# DIGI_PTT_CW.net
KiCad netlist of a schematic drawn in EAGLE
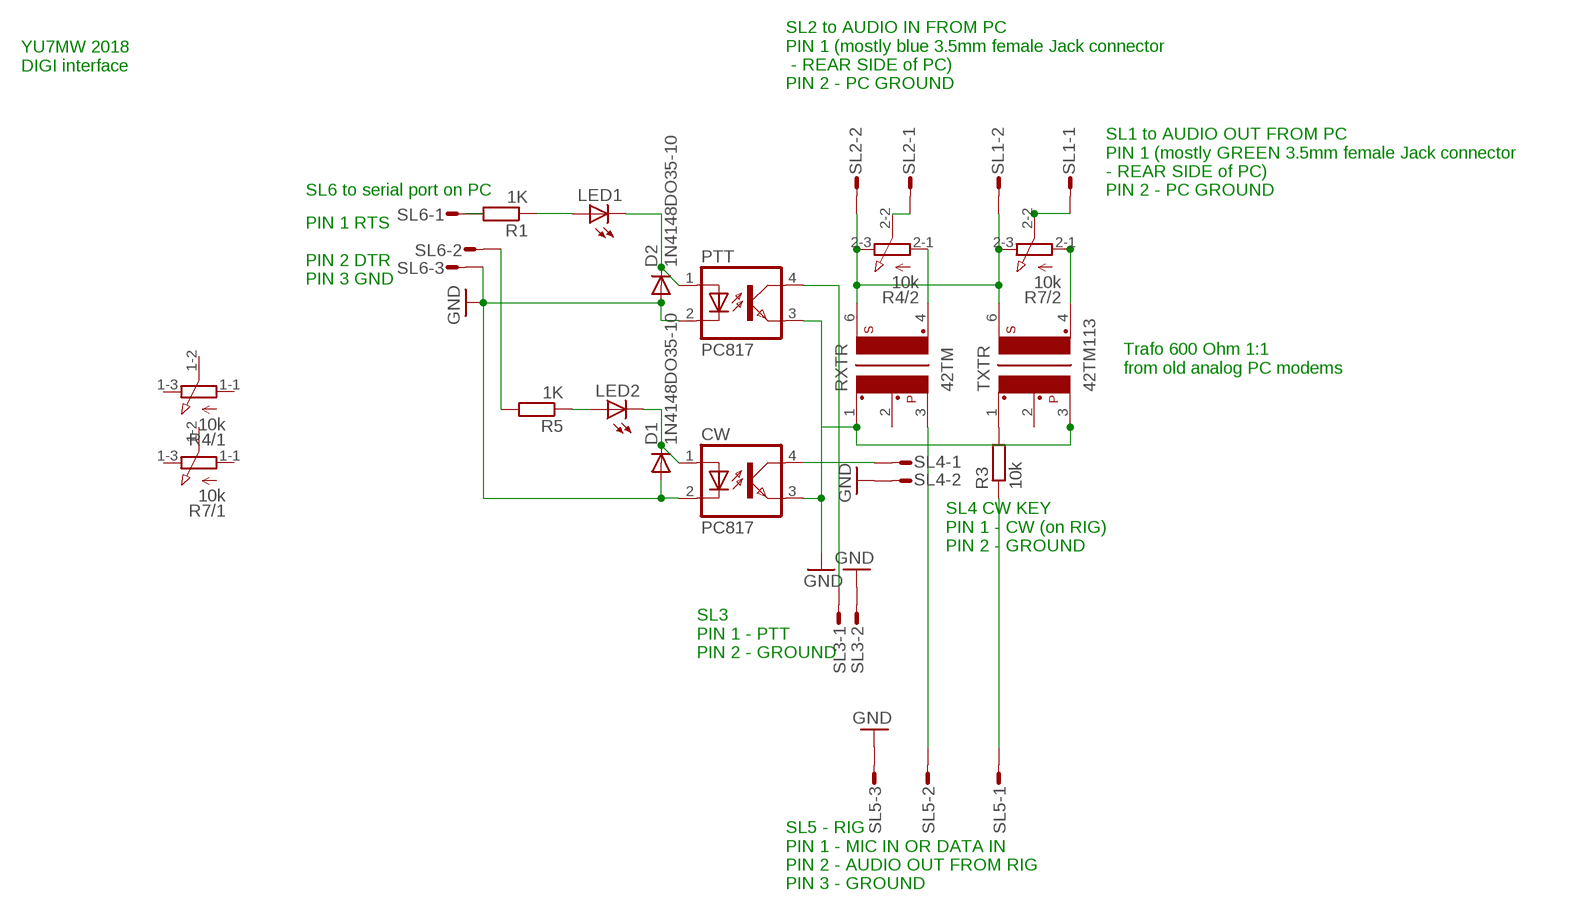
[diagram p0: schematic, sheet 1]

(export (version "E")
  (design (tool "Eeschema 10.0.6"))
  (components
    (comp (ref "CW")
      (value "PC817")
      (footprint "eagle-import:DIL04")
      (fields (field (name "MPN") "PC817X4J000F"))
      (libsource (lib "eagle-import") (part "PC817"))
    )
    (comp (ref "D1")
      (value "1N4148DO35-10")
      (footprint "eagle-import:DO35-10")
      (libsource (lib "eagle-import") (part "1N4148DO35-10"))
    )
    (comp (ref "D2")
      (value "1N4148DO35-10")
      (footprint "eagle-import:DO35-10")
      (libsource (lib "eagle-import") (part "1N4148DO35-10"))
    )
    (comp (ref "LED1")
      (value "LED3MM")
      (footprint "eagle-import:LED3MM")
      (libsource (lib "eagle-import") (part "LED3MM"))
    )
    (comp (ref "LED2")
      (value "LED3MM")
      (footprint "eagle-import:LED3MM")
      (libsource (lib "eagle-import") (part "LED3MM"))
    )
    (comp (ref "PTT")
      (value "PC817")
      (footprint "eagle-import:DIL04")
      (fields (field (name "MPN") "PC817X4J000F"))
      (libsource (lib "eagle-import") (part "PC817"))
    )
    (comp (ref "R1")
      (value "1K")
      (footprint "eagle-import:0207_10")
      (libsource (lib "eagle-import") (part "R-EU_0207/10"))
    )
    (comp (ref "R3")
      (value "10k")
      (footprint "eagle-import:0207_10")
      (libsource (lib "eagle-import") (part "R-EU_0207/10"))
    )
    (comp (ref "R4")
      (value "10k")
      (footprint "eagle-import:3RP_1610G")
      (libsource (lib "eagle-import") (part "3RP/1610G"))
    )
    (comp (ref "R5")
      (value "1K")
      (footprint "eagle-import:0207_10")
      (libsource (lib "eagle-import") (part "R-EU_0207/10"))
    )
    (comp (ref "R7")
      (value "10k")
      (footprint "eagle-import:3RP_1610G")
      (libsource (lib "eagle-import") (part "3RP/1610G"))
    )
    (comp (ref "RXTR")
      (value "42TM")
      (footprint "eagle-import:42TM")
      (libsource (lib "eagle-import") (part "42TM113"))
    )
    (comp (ref "SL1")
      (value "M02S")
      (footprint "eagle-import:02P")
      (libsource (lib "eagle-import") (part "M02S"))
    )
    (comp (ref "SL2")
      (value "M02S")
      (footprint "eagle-import:02P")
      (libsource (lib "eagle-import") (part "M02S"))
    )
    (comp (ref "SL3")
      (value "M02S")
      (footprint "eagle-import:02P")
      (libsource (lib "eagle-import") (part "M02S"))
    )
    (comp (ref "SL4")
      (value "M02S")
      (footprint "eagle-import:02P")
      (libsource (lib "eagle-import") (part "M02S"))
    )
    (comp (ref "SL5")
      (value "M03S")
      (footprint "eagle-import:03P")
      (libsource (lib "eagle-import") (part "M03S"))
    )
    (comp (ref "SL6")
      (value "M03S")
      (footprint "eagle-import:03P")
      (libsource (lib "eagle-import") (part "M03S"))
    )
    (comp (ref "TXTR")
      (value "42TM113")
      (footprint "eagle-import:42TM")
      (libsource (lib "eagle-import") (part "42TM113"))
    )
  )
  (nets
    (net (code "1") (name "GND") (class "Default")
      (node (ref "CW") (pin "2") (pinfunction "C_2") (pintype "passive"))
      (node (ref "CW") (pin "3") (pinfunction "EMIT_3") (pintype "passive"))
      (node (ref "D1") (pin "A") (pinfunction "A_A") (pintype "passive"))
      (node (ref "D2") (pin "A") (pinfunction "A_A") (pintype "passive"))
      (node (ref "PTT") (pin "2") (pinfunction "C_2") (pintype "passive"))
      (node (ref "PTT") (pin "3") (pinfunction "EMIT_3") (pintype "passive"))
      (node (ref "RXTR") (pin "1") (pinfunction "1_1") (pintype "passive"))
      (node (ref "SL3") (pin "2") (pinfunction "S_2") (pintype "passive"))
      (node (ref "SL4") (pin "2") (pinfunction "S_2") (pintype "passive"))
      (node (ref "SL5") (pin "3") (pinfunction "S_3") (pintype "passive"))
      (node (ref "SL6") (pin "3") (pinfunction "S_3") (pintype "passive"))
      (node (ref "TXTR") (pin "3") (pinfunction "3_3") (pintype "passive"))
    )
    (net (code "2") (name "Net-(CW-A)") (class "Default")
      (node (ref "CW") (pin "1") (pinfunction "A_1") (pintype "passive"))
      (node (ref "D1") (pin "C") (pinfunction "C_C") (pintype "passive"))
      (node (ref "LED2") (pin "K") (pinfunction "C_K") (pintype "passive"))
    )
    (net (code "3") (name "Net-(CW-COL)") (class "Default")
      (node (ref "CW") (pin "4") (pinfunction "COL_4") (pintype "passive"))
      (node (ref "SL4") (pin "1") (pinfunction "S_1") (pintype "passive"))
    )
    (net (code "4") (name "Net-(LED1-C)") (class "Default")
      (node (ref "D2") (pin "C") (pinfunction "C_C") (pintype "passive"))
      (node (ref "LED1") (pin "K") (pinfunction "C_K") (pintype "passive"))
      (node (ref "PTT") (pin "1") (pinfunction "A_1") (pintype "passive"))
    )
    (net (code "5") (name "Net-(LED1-PadA)") (class "Default")
      (node (ref "LED1") (pin "A") (pinfunction "A_A") (pintype "passive"))
      (node (ref "R1") (pin "1") (pinfunction "1_1") (pintype "passive"))
    )
    (net (code "6") (name "Net-(LED2-PadA)") (class "Default")
      (node (ref "LED2") (pin "A") (pinfunction "A_A") (pintype "passive"))
      (node (ref "R5") (pin "1") (pinfunction "1_1") (pintype "passive"))
    )
    (net (code "7") (name "Net-(PTT-COL)") (class "Default")
      (node (ref "PTT") (pin "4") (pinfunction "COL_4") (pintype "passive"))
      (node (ref "SL3") (pin "1") (pinfunction "S_1") (pintype "passive"))
    )
    (net (code "8") (name "Net-(R3-Pad2)") (class "Default")
      (node (ref "R3") (pin "2") (pinfunction "2_2") (pintype "passive"))
      (node (ref "TXTR") (pin "1") (pinfunction "1_1") (pintype "passive"))
    )
    (net (code "9") (name "Net-(R4B-A)") (class "Default")
      (node (ref "R4") (pin "2-1") (pinfunction "A_2-1") (pintype "passive"))
      (node (ref "RXTR") (pin "4") (pinfunction "4_4") (pintype "passive"))
    )
    (net (code "10") (name "Net-(R4B-E)") (class "Default")
      (node (ref "R4") (pin "2-3") (pinfunction "E_2-3") (pintype "passive"))
      (node (ref "R7") (pin "2-3") (pinfunction "E_2-3") (pintype "passive"))
      (node (ref "RXTR") (pin "6") (pinfunction "6_6") (pintype "passive"))
      (node (ref "SL1") (pin "2") (pinfunction "S_2") (pintype "passive"))
      (node (ref "SL2") (pin "2") (pinfunction "S_2") (pintype "passive"))
      (node (ref "TXTR") (pin "6") (pinfunction "6_6") (pintype "passive"))
    )
    (net (code "11") (name "Net-(R4B-S)") (class "Default")
      (node (ref "R4") (pin "2-2") (pinfunction "S_2-2") (pintype "passive"))
      (node (ref "SL2") (pin "1") (pinfunction "S_1") (pintype "passive"))
    )
    (net (code "12") (name "Net-(R7B-A)") (class "Default")
      (node (ref "R7") (pin "2-1") (pinfunction "A_2-1") (pintype "passive"))
      (node (ref "TXTR") (pin "4") (pinfunction "4_4") (pintype "passive"))
    )
    (net (code "13") (name "Net-(R7B-S)") (class "Default")
      (node (ref "R7") (pin "2-2") (pinfunction "S_2-2") (pintype "passive"))
      (node (ref "SL1") (pin "1") (pinfunction "S_1") (pintype "passive"))
    )
    (net (code "14") (name "Net-(SL5A-S)") (class "Default")
      (node (ref "R3") (pin "1") (pinfunction "1_1") (pintype "passive"))
      (node (ref "SL5") (pin "1") (pinfunction "S_1") (pintype "passive"))
    )
    (net (code "15") (name "Net-(SL5B-S)") (class "Default")
      (node (ref "RXTR") (pin "3") (pinfunction "3_3") (pintype "passive"))
      (node (ref "SL5") (pin "2") (pinfunction "S_2") (pintype "passive"))
    )
    (net (code "16") (name "Net-(SL6A-S)") (class "Default")
      (node (ref "R1") (pin "2") (pinfunction "2_2") (pintype "passive"))
      (node (ref "SL6") (pin "1") (pinfunction "S_1") (pintype "passive"))
    )
    (net (code "17") (name "Net-(SL6B-S)") (class "Default")
      (node (ref "R5") (pin "2") (pinfunction "2_2") (pintype "passive"))
      (node (ref "SL6") (pin "2") (pinfunction "S_2") (pintype "passive"))
    )
    (net (code "18") (name "unconnected-(R4A-A-Pad1-1)") (class "Default")
      (node (ref "R4") (pin "1-1") (pinfunction "A_1-1") (pintype "passive"))
    )
    (net (code "19") (name "unconnected-(R4A-E-Pad1-3)") (class "Default")
      (node (ref "R4") (pin "1-3") (pinfunction "E_1-3") (pintype "passive"))
    )
    (net (code "20") (name "unconnected-(R4A-S-Pad1-2)") (class "Default")
      (node (ref "R4") (pin "1-2") (pinfunction "S_1-2") (pintype "passive"))
    )
    (net (code "21") (name "unconnected-(R7A-A-Pad1-1)") (class "Default")
      (node (ref "R7") (pin "1-1") (pinfunction "A_1-1") (pintype "passive"))
    )
    (net (code "22") (name "unconnected-(R7A-E-Pad1-3)") (class "Default")
      (node (ref "R7") (pin "1-3") (pinfunction "E_1-3") (pintype "passive"))
    )
    (net (code "23") (name "unconnected-(R7A-S-Pad1-2)") (class "Default")
      (node (ref "R7") (pin "1-2") (pinfunction "S_1-2") (pintype "passive"))
    )
    (net (code "24") (name "unconnected-(RXTR-Pad2)") (class "Default")
      (node (ref "RXTR") (pin "2") (pinfunction "2_2") (pintype "passive"))
    )
    (net (code "25") (name "unconnected-(TXTR-Pad2)") (class "Default")
      (node (ref "TXTR") (pin "2") (pinfunction "2_2") (pintype "passive"))
    )
  )
)
